# main_board_mcu.net
KiCad netlist of a schematic drawn in Altium Designer
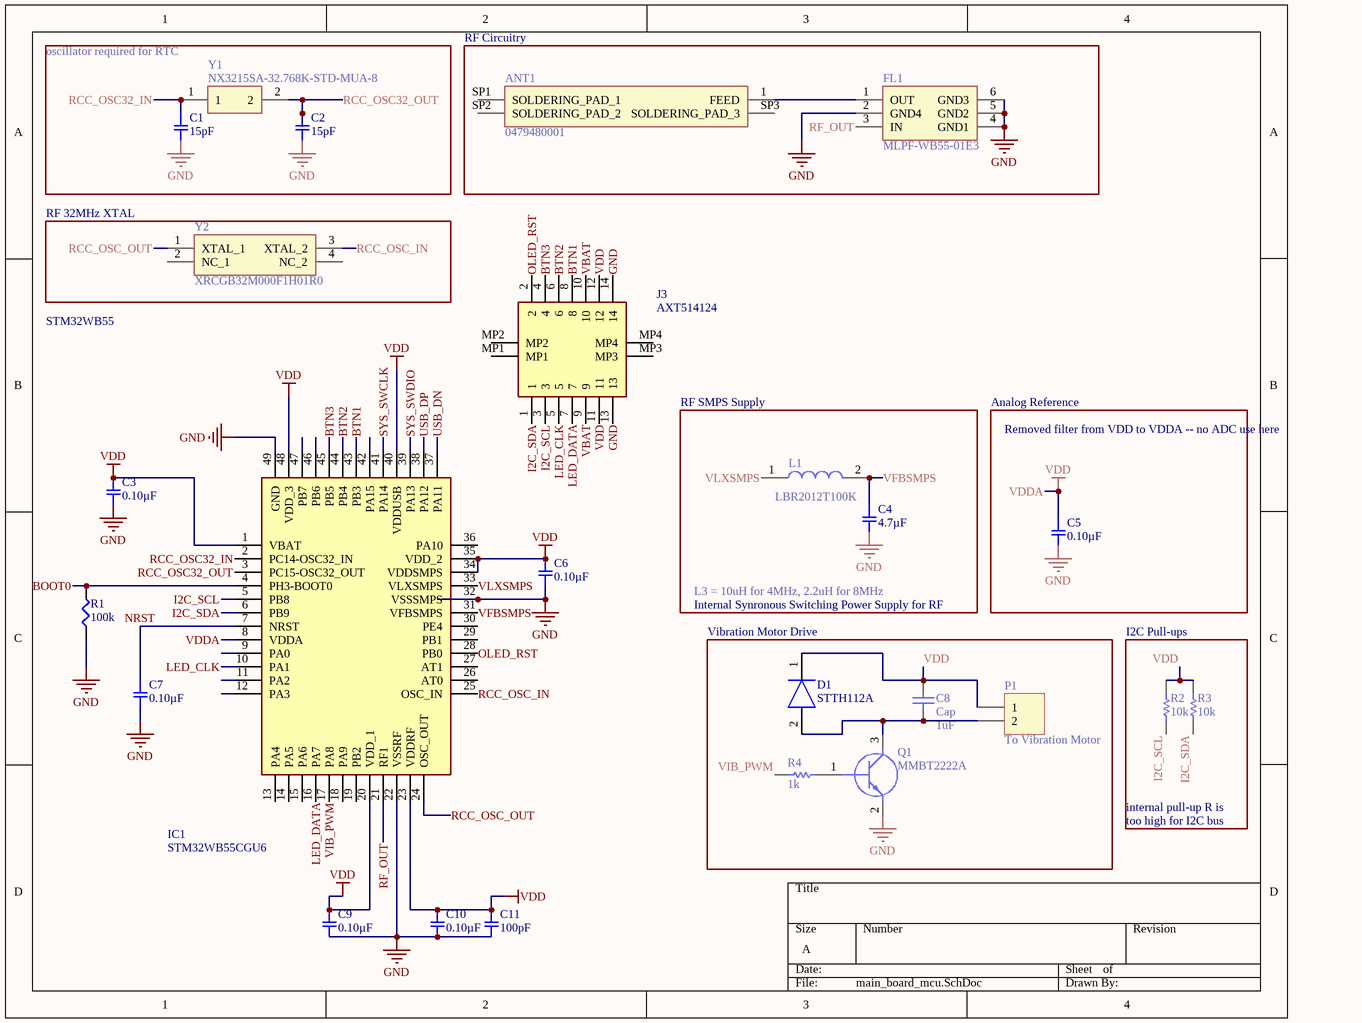
[diagram p0: main_board_mcu.SchDoc]

(export (version "E")
  (design (tool "Eeschema 10.0.6"))
  (components
    (comp (ref "ANT1")
      (value "0479480001")
      (footprint "SamacSys:0479480001")
      (description "Antenna")
      (libsource (lib "*") (part "0479480001"))
    )
    (comp (ref "C1")
      (value "15pF")
      (footprint "0402C")
      (description "CAP CER 15PF 50V NP0 0402")
      (fields
        (field (name "DIGI-KEY PART NUMBER") "490-11147-1-ND")
        (field (name "PART NUMBER") "GCM1555C1H150JA16D")
      )
      (libsource (lib "capacitor_murata_0402") (part "GCM1555C1H150JA16D"))
    )
    (comp (ref "C2")
      (value "15pF")
      (footprint "0402C")
      (description "CAP CER 15PF 50V NP0 0402")
      (fields
        (field (name "DIGI-KEY PART NUMBER") "490-11147-1-ND")
        (field (name "PART NUMBER") "GCM1555C1H150JA16D")
      )
      (libsource (lib "capacitor_murata_0402") (part "GCM1555C1H150JA16D"))
    )
    (comp (ref "C3")
      (value "0.10µF")
      (footprint "0402C")
      (description "CAP CER 0.1UF 16V X7R 0402")
      (fields
        (field (name "DIGI-KEY PART NUMBER") "490-4759-1-ND")
        (field (name "PART NUMBER") "GCM155R71C104KA55D")
      )
      (libsource (lib "capacitor_murata_0402") (part "GCM155R71C104KA55D"))
    )
    (comp (ref "C4")
      (value "4.7µF")
      (footprint "0402C")
      (description "CAP CER 4.7UF 4V X5R 0402")
      (fields
        (field (name "DIGI-KEY PART NUMBER") "490-13231-1-ND")
        (field (name "PART NUMBER") "GRM153R60G475ME15D")
      )
      (libsource (lib "capacitor_murata_0402") (part "GRM153R60G475ME15D"))
    )
    (comp (ref "C5")
      (value "0.10µF")
      (footprint "0402C")
      (description "CAP CER 0.1UF 16V X7R 0402")
      (fields
        (field (name "DIGI-KEY PART NUMBER") "490-4759-1-ND")
        (field (name "PART NUMBER") "GCM155R71C104KA55D")
      )
      (libsource (lib "capacitor_murata_0402") (part "GCM155R71C104KA55D"))
    )
    (comp (ref "C6")
      (value "0.10µF")
      (footprint "0402C")
      (description "CAP CER 0.1UF 16V X7R 0402")
      (fields
        (field (name "DIGI-KEY PART NUMBER") "490-4759-1-ND")
        (field (name "PART NUMBER") "GCM155R71C104KA55D")
      )
      (libsource (lib "capacitor_murata_0402") (part "GCM155R71C104KA55D"))
    )
    (comp (ref "C7")
      (value "0.10µF")
      (footprint "0402C")
      (description "CAP CER 0.1UF 16V X7R 0402")
      (fields
        (field (name "DIGI-KEY PART NUMBER") "490-4759-1-ND")
        (field (name "PART NUMBER") "GCM155R71C104KA55D")
      )
      (libsource (lib "capacitor_murata_0402") (part "GCM155R71C104KA55D"))
    )
    (comp (ref "C8")
      (value "Cap")
      (footprint "0402C")
      (description "Capacitor")
      (fields (field (name "ALTIUM_VALUE") "1uF") (field (name "PUBLISHER") "Altium Limited"))
      (libsource (lib "Miscellaneous Devices") (part "Cap"))
    )
    (comp (ref "C9")
      (value "0.10µF")
      (footprint "0402C")
      (description "CAP CER 0.1UF 16V X7R 0402")
      (fields
        (field (name "DIGI-KEY PART NUMBER") "490-4759-1-ND")
        (field (name "PART NUMBER") "GCM155R71C104KA55D")
      )
      (libsource (lib "capacitor_murata_0402") (part "GCM155R71C104KA55D"))
    )
    (comp (ref "C10")
      (value "0.10µF")
      (footprint "0402C")
      (description "CAP CER 0.1UF 16V X7R 0402")
      (fields
        (field (name "DIGI-KEY PART NUMBER") "490-4759-1-ND")
        (field (name "PART NUMBER") "GCM155R71C104KA55D")
      )
      (libsource (lib "capacitor_murata_0402") (part "GCM155R71C104KA55D"))
    )
    (comp (ref "C11")
      (value "100pF")
      (footprint "0402C")
      (description "CAP CER 100PF 50V NP0 0402")
      (fields
        (field (name "DIGI-KEY PART NUMBER") "490-10669-1-ND")
        (field (name "PART NUMBER") "GCM1555C1H101JA16D")
      )
      (libsource (lib "capacitor_murata_0402") (part "GCM1555C1H101JA16D"))
    )
    (comp (ref "D1")
      (value "STTH112A")
      (footprint "SamacSys:DIOM5126X265N")
      (description "Diode")
      (fields (field (name "MOUSER PART NUMBER") "511-STTH112A") (field (name "RS PART NUMBER") "0249319"))
      (libsource (lib "*") (part "STTH112A"))
    )
    (comp (ref "FL1")
      (value "MLPF-WB55-01E3")
      (footprint "SamacSys:MLPFWB5501E3")
      (description "Filter")
      (fields
        (field (name "MOUSER PART NUMBER") "511-MLPF-WB55-01E3")
        (field (name "RS PART NUMBER") "1924203")
      )
      (libsource (lib "*") (part "MLPF-WB55-01E3"))
    )
    (comp (ref "IC1")
      (value "STM32WB55CGU6")
      (footprint "QFN50P700X700X65-49N-D")
      (description "Integrated Circuit")
      (fields (field (name "MOUSER PART NUMBER") "511-STM32WB55CGU6"))
      (libsource (lib "SamacSys") (part "STM32WB55CGU6"))
    )
    (comp (ref "J3")
      (value "AXT514124")
      (footprint "SamacSys:AXT514124")
      (description "Connector")
      (fields (field (name "MOUSER PART NUMBER") "769-AXT514124"))
      (libsource (lib "*") (part "AXT514124"))
    )
    (comp (ref "L1")
      (value "LBR2012T100K")
      (footprint "INDC2012X145N")
      (description "Inductor")
      (fields (field (name "MOUSER PART NUMBER") "963-LBR2012T100K"))
      (libsource (lib "SamacSys") (part "LBR2012T100K"))
    )
    (comp (ref "P1")
      (value "To Vibration Motor")
      (footprint "HDR1X2")
      (description "Header, 2-Pin")
      (fields (field (name "PUBLISHER") "Altium Limited"))
      (libsource (lib "Miscellaneous Connectors") (part "Header 2"))
    )
    (comp (ref "Q1")
      (value "MMBT2222A")
      (footprint "SamacSys:SOT95P240X120-3N")
      (description "Transistor BJT NPN")
      (fields (field (name "MOUSER PART NUMBER") "512-MMBT2222A") (field (name "RS PART NUMBER") "7390350P"))
      (libsource (lib "*") (part "MMBT2222A"))
    )
    (comp (ref "R1")
      (value "100k")
      (footprint "0402R")
      (description "RES SMD 100K OHM 1% 1/10W 0402")
      (fields
        (field (name "PART NUMBER") "ERJ-2RKF1003X")
        (field (name "DIGI-KEY PART NUMBER") "P100KLCT-ND")
      )
      (libsource (lib "Panasonic_ERJ_0402") (part "ERJ-2RKF1003X"))
    )
    (comp (ref "R2")
      (value "10k")
      (footprint "0402R")
      (libsource (lib "glasses_full_v1_small") (part "Resistor"))
    )
    (comp (ref "R3")
      (value "10k")
      (footprint "0402R")
      (libsource (lib "glasses_full_v1_small") (part "Resistor"))
    )
    (comp (ref "R4")
      (value "1k")
      (footprint "0402R")
      (libsource (lib "glasses_full_v1_small") (part "Resistor"))
    )
    (comp (ref "Y1")
      (value "NX3215SA-32.768K-STD-MUA-8")
      (footprint "NX3215SA")
      (description "Crystal or Oscillator")
      (fields (field (name "MOUSER PART NUMBER") "344-NX3215SA32768K8"))
      (libsource (lib "SamacSys") (part "NX3215SA-32.768K-STD-MUA-8"))
    )
    (comp (ref "Y2")
      (value "XRCGB32M000F1H01R0")
      (footprint "XRCGB32M000F1H01R0")
      (description "Crystal or Oscillator")
      (fields (field (name "MOUSER PART NUMBER") "81-XRCGB32M000F1H01R"))
      (libsource (lib "SamacSys") (part "XRCGB32M000F1H01R0"))
    )
  )
  (nets
    (net (code "1") (name "/BOOT0") (class "Default")
      (node (ref "IC1") (pin "4") (pinfunction "PH3-BOOT0_4") (pintype "passive"))
      (node (ref "R1") (pin "2") (pinfunction "2_2") (pintype "passive"))
    )
    (net (code "2") (name "/BTN1") (class "Default")
      (node (ref "IC1") (pin "43") (pinfunction "PB3_43") (pintype "passive"))
      (node (ref "J3") (pin "8") (pinfunction "8_8") (pintype "passive"))
    )
    (net (code "3") (name "/BTN2") (class "Default")
      (node (ref "IC1") (pin "44") (pinfunction "PB4_44") (pintype "passive"))
      (node (ref "J3") (pin "6") (pinfunction "6_6") (pintype "passive"))
    )
    (net (code "4") (name "/BTN3") (class "Default")
      (node (ref "IC1") (pin "45") (pinfunction "PB5_45") (pintype "passive"))
      (node (ref "J3") (pin "4") (pinfunction "4_4") (pintype "passive"))
    )
    (net (code "5") (name "/I2C_SCL") (class "Default")
      (node (ref "IC1") (pin "5") (pinfunction "PB8_5") (pintype "passive"))
      (node (ref "J3") (pin "3") (pinfunction "3_3") (pintype "passive"))
      (node (ref "R2") (pin "2") (pinfunction "2_2") (pintype "passive"))
    )
    (net (code "6") (name "/I2C_SDA") (class "Default")
      (node (ref "IC1") (pin "6") (pinfunction "PB9_6") (pintype "passive"))
      (node (ref "J3") (pin "1") (pinfunction "1_1") (pintype "passive"))
      (node (ref "R3") (pin "2") (pinfunction "2_2") (pintype "passive"))
    )
    (net (code "7") (name "/LED_CLK") (class "Default")
      (node (ref "IC1") (pin "10") (pinfunction "PA1_10") (pintype "passive"))
      (node (ref "J3") (pin "5") (pinfunction "5_5") (pintype "passive"))
    )
    (net (code "8") (name "/LED_DATA") (class "Default")
      (node (ref "IC1") (pin "16") (pinfunction "PA7_16") (pintype "passive"))
      (node (ref "J3") (pin "7") (pinfunction "7_7") (pintype "passive"))
    )
    (net (code "9") (name "/NRST") (class "Default")
      (node (ref "C7") (pin "1") (pinfunction "1_1") (pintype "passive"))
      (node (ref "IC1") (pin "7") (pinfunction "NRST_7") (pintype "passive"))
    )
    (net (code "10") (name "/OLED_RST") (class "Default")
      (node (ref "IC1") (pin "28") (pinfunction "PB0_28") (pintype "passive"))
      (node (ref "J3") (pin "2") (pinfunction "2_2") (pintype "passive"))
    )
    (net (code "11") (name "/RCC_OSC32_IN") (class "Default")
      (node (ref "C1") (pin "1") (pinfunction "1_1") (pintype "passive"))
      (node (ref "IC1") (pin "2") (pinfunction "PC14-OSC32_IN_2") (pintype "passive"))
      (node (ref "Y1") (pin "1") (pinfunction "1_1") (pintype "passive"))
    )
    (net (code "12") (name "/RCC_OSC32_OUT") (class "Default")
      (node (ref "C2") (pin "1") (pinfunction "1_1") (pintype "passive"))
      (node (ref "IC1") (pin "3") (pinfunction "PC15-OSC32_OUT_3") (pintype "passive"))
      (node (ref "Y1") (pin "2") (pinfunction "2_2") (pintype "passive"))
    )
    (net (code "13") (name "/RCC_OSC_IN") (class "Default")
      (node (ref "IC1") (pin "25") (pinfunction "OSC_IN_25") (pintype "passive"))
      (node (ref "Y2") (pin "3") (pinfunction "XTAL_2_3") (pintype "passive"))
    )
    (net (code "14") (name "/RCC_OSC_OUT") (class "Default")
      (node (ref "IC1") (pin "24") (pinfunction "OSC_OUT_24") (pintype "passive"))
      (node (ref "Y2") (pin "1") (pinfunction "XTAL_1_1") (pintype "passive"))
    )
    (net (code "15") (name "/RF_OUT") (class "Default")
      (node (ref "FL1") (pin "3") (pinfunction "IN_3") (pintype "passive"))
      (node (ref "IC1") (pin "21") (pinfunction "RF1_21") (pintype "passive"))
    )
    (net (code "16") (name "/SYS_SWCLK") (class "Default")
      (node (ref "IC1") (pin "41") (pinfunction "PA14_41") (pintype "passive"))
    )
    (net (code "17") (name "/SYS_SWDIO") (class "Default")
      (node (ref "IC1") (pin "39") (pinfunction "PA13_39") (pintype "passive"))
    )
    (net (code "18") (name "/USB_DN") (class "Default")
      (node (ref "IC1") (pin "37") (pinfunction "PA11_37") (pintype "passive"))
    )
    (net (code "19") (name "/USB_DP") (class "Default")
      (node (ref "IC1") (pin "38") (pinfunction "PA12_38") (pintype "passive"))
    )
    (net (code "20") (name "/VBAT") (class "Default")
      (node (ref "J3") (pin "10") (pinfunction "10_10") (pintype "passive"))
      (node (ref "J3") (pin "9") (pinfunction "9_9") (pintype "passive"))
    )
    (net (code "21") (name "/VFBSMPS") (class "Default")
      (node (ref "C4") (pin "1") (pinfunction "1_1") (pintype "passive"))
      (node (ref "IC1") (pin "31") (pinfunction "VFBSMPS_31") (pintype "passive"))
      (node (ref "L1") (pin "2") (pinfunction "2_2") (pintype "passive"))
    )
    (net (code "22") (name "/VIB_PWM") (class "Default")
      (node (ref "IC1") (pin "17") (pinfunction "PA8_17") (pintype "passive"))
      (node (ref "R4") (pin "2") (pinfunction "2_2") (pintype "passive"))
    )
    (net (code "23") (name "/VLXSMPS") (class "Default")
      (node (ref "IC1") (pin "33") (pinfunction "VLXSMPS_33") (pintype "passive"))
      (node (ref "L1") (pin "1") (pinfunction "1_1") (pintype "passive"))
    )
    (net (code "24") (name "GND") (class "Default")
      (node (ref "C1") (pin "2") (pinfunction "2_2") (pintype "passive"))
      (node (ref "C10") (pin "2") (pinfunction "2_2") (pintype "passive"))
      (node (ref "C11") (pin "2") (pinfunction "2_2") (pintype "passive"))
      (node (ref "C2") (pin "2") (pinfunction "2_2") (pintype "passive"))
      (node (ref "C3") (pin "2") (pinfunction "2_2") (pintype "passive"))
      (node (ref "C4") (pin "2") (pinfunction "2_2") (pintype "passive"))
      (node (ref "C5") (pin "2") (pinfunction "2_2") (pintype "passive"))
      (node (ref "C6") (pin "2") (pinfunction "2_2") (pintype "passive"))
      (node (ref "C7") (pin "2") (pinfunction "2_2") (pintype "passive"))
      (node (ref "C9") (pin "2") (pinfunction "2_2") (pintype "passive"))
      (node (ref "FL1") (pin "2") (pinfunction "GND4_2") (pintype "passive"))
      (node (ref "FL1") (pin "4") (pinfunction "GND1_4") (pintype "passive"))
      (node (ref "FL1") (pin "5") (pinfunction "GND2_5") (pintype "passive"))
      (node (ref "FL1") (pin "6") (pinfunction "GND3_6") (pintype "passive"))
      (node (ref "IC1") (pin "22") (pinfunction "VSSRF_22") (pintype "passive"))
      (node (ref "IC1") (pin "32") (pinfunction "VSSSMPS_32") (pintype "passive"))
      (node (ref "IC1") (pin "49") (pinfunction "GND_49") (pintype "passive"))
      (node (ref "J3") (pin "13") (pinfunction "13_13") (pintype "passive"))
      (node (ref "J3") (pin "14") (pinfunction "14_14") (pintype "passive"))
      (node (ref "Q1") (pin "2") (pinfunction "E_2") (pintype "passive"))
      (node (ref "R1") (pin "1") (pinfunction "1_1") (pintype "passive"))
    )
    (net (code "25") (name "Net-(ANT1-FEED)") (class "Default")
      (node (ref "ANT1") (pin "1") (pinfunction "FEED_1") (pintype "passive"))
      (node (ref "FL1") (pin "1") (pinfunction "OUT_1") (pintype "passive"))
    )
    (net (code "26") (name "Net-(D1-A)") (class "Default")
      (node (ref "C8") (pin "1") (pinfunction "1_1") (pintype "passive"))
      (node (ref "D1") (pin "2") (pinfunction "A_2") (pintype "passive"))
      (node (ref "P1") (pin "2") (pinfunction "2_2") (pintype "passive"))
      (node (ref "Q1") (pin "3") (pinfunction "C_3") (pintype "passive"))
    )
    (net (code "27") (name "Net-(Q1-B)") (class "Default")
      (node (ref "Q1") (pin "1") (pinfunction "B_1") (pintype "passive"))
      (node (ref "R4") (pin "1") (pinfunction "1_1") (pintype "passive"))
    )
    (net (code "28") (name "VDD") (class "Default")
      (node (ref "C10") (pin "1") (pinfunction "1_1") (pintype "passive"))
      (node (ref "C11") (pin "1") (pinfunction "1_1") (pintype "passive"))
      (node (ref "C3") (pin "1") (pinfunction "1_1") (pintype "passive"))
      (node (ref "C5") (pin "1") (pinfunction "1_1") (pintype "passive"))
      (node (ref "C6") (pin "1") (pinfunction "1_1") (pintype "passive"))
      (node (ref "C8") (pin "2") (pinfunction "2_2") (pintype "passive"))
      (node (ref "C9") (pin "1") (pinfunction "1_1") (pintype "passive"))
      (node (ref "D1") (pin "1") (pinfunction "K_1") (pintype "passive"))
      (node (ref "IC1") (pin "1") (pinfunction "VBAT_1") (pintype "passive"))
      (node (ref "IC1") (pin "20") (pinfunction "VDD_1_20") (pintype "passive"))
      (node (ref "IC1") (pin "23") (pinfunction "VDDRF_23") (pintype "passive"))
      (node (ref "IC1") (pin "34") (pinfunction "VDDSMPS_34") (pintype "passive"))
      (node (ref "IC1") (pin "35") (pinfunction "VDD_2_35") (pintype "passive"))
      (node (ref "IC1") (pin "40") (pinfunction "VDDUSB_40") (pintype "passive"))
      (node (ref "IC1") (pin "48") (pinfunction "VDD_3_48") (pintype "passive"))
      (node (ref "IC1") (pin "8") (pinfunction "VDDA_8") (pintype "passive"))
      (node (ref "J3") (pin "11") (pinfunction "11_11") (pintype "passive"))
      (node (ref "J3") (pin "12") (pinfunction "12_12") (pintype "passive"))
      (node (ref "P1") (pin "1") (pinfunction "1_1") (pintype "passive"))
      (node (ref "R2") (pin "1") (pinfunction "1_1") (pintype "passive"))
      (node (ref "R3") (pin "1") (pinfunction "1_1") (pintype "passive"))
    )
    (net (code "29") (name "unconnected-(ANT1-SOLDERING_PAD_1-PadSP1)") (class "Default")
      (node (ref "ANT1") (pin "SP1") (pinfunction "SOLDERING_PAD_1_SP1") (pintype "passive"))
    )
    (net (code "30") (name "unconnected-(ANT1-SOLDERING_PAD_2-PadSP2)") (class "Default")
      (node (ref "ANT1") (pin "SP2") (pinfunction "SOLDERING_PAD_2_SP2") (pintype "passive"))
    )
    (net (code "31") (name "unconnected-(ANT1-SOLDERING_PAD_3-PadSP3)") (class "Default")
      (node (ref "ANT1") (pin "SP3") (pinfunction "SOLDERING_PAD_3_SP3") (pintype "passive"))
    )
    (net (code "32") (name "unconnected-(IC1-AT0-Pad26)") (class "Default")
      (node (ref "IC1") (pin "26") (pinfunction "AT0_26") (pintype "passive"))
    )
    (net (code "33") (name "unconnected-(IC1-AT1-Pad27)") (class "Default")
      (node (ref "IC1") (pin "27") (pinfunction "AT1_27") (pintype "passive"))
    )
    (net (code "34") (name "unconnected-(IC1-PA0-Pad9)") (class "Default")
      (node (ref "IC1") (pin "9") (pinfunction "PA0_9") (pintype "passive"))
    )
    (net (code "35") (name "unconnected-(IC1-PA2-Pad11)") (class "Default")
      (node (ref "IC1") (pin "11") (pinfunction "PA2_11") (pintype "passive"))
    )
    (net (code "36") (name "unconnected-(IC1-PA3-Pad12)") (class "Default")
      (node (ref "IC1") (pin "12") (pinfunction "PA3_12") (pintype "passive"))
    )
    (net (code "37") (name "unconnected-(IC1-PA4-Pad13)") (class "Default")
      (node (ref "IC1") (pin "13") (pinfunction "PA4_13") (pintype "passive"))
    )
    (net (code "38") (name "unconnected-(IC1-PA5-Pad14)") (class "Default")
      (node (ref "IC1") (pin "14") (pinfunction "PA5_14") (pintype "passive"))
    )
    (net (code "39") (name "unconnected-(IC1-PA6-Pad15)") (class "Default")
      (node (ref "IC1") (pin "15") (pinfunction "PA6_15") (pintype "passive"))
    )
    (net (code "40") (name "unconnected-(IC1-PA9-Pad18)") (class "Default")
      (node (ref "IC1") (pin "18") (pinfunction "PA9_18") (pintype "passive"))
    )
    (net (code "41") (name "unconnected-(IC1-PA10-Pad36)") (class "Default")
      (node (ref "IC1") (pin "36") (pinfunction "PA10_36") (pintype "passive"))
    )
    (net (code "42") (name "unconnected-(IC1-PA15-Pad42)") (class "Default")
      (node (ref "IC1") (pin "42") (pinfunction "PA15_42") (pintype "passive"))
    )
    (net (code "43") (name "unconnected-(IC1-PB1-Pad29)") (class "Default")
      (node (ref "IC1") (pin "29") (pinfunction "PB1_29") (pintype "passive"))
    )
    (net (code "44") (name "unconnected-(IC1-PB2-Pad19)") (class "Default")
      (node (ref "IC1") (pin "19") (pinfunction "PB2_19") (pintype "passive"))
    )
    (net (code "45") (name "unconnected-(IC1-PB6-Pad46)") (class "Default")
      (node (ref "IC1") (pin "46") (pinfunction "PB6_46") (pintype "passive"))
    )
    (net (code "46") (name "unconnected-(IC1-PB7-Pad47)") (class "Default")
      (node (ref "IC1") (pin "47") (pinfunction "PB7_47") (pintype "passive"))
    )
    (net (code "47") (name "unconnected-(IC1-PE4-Pad30)") (class "Default")
      (node (ref "IC1") (pin "30") (pinfunction "PE4_30") (pintype "passive"))
    )
    (net (code "48") (name "unconnected-(J3-PadMP1)") (class "Default")
      (node (ref "J3") (pin "MP1") (pinfunction "MP1_MP1") (pintype "passive"))
    )
    (net (code "49") (name "unconnected-(J3-PadMP2)") (class "Default")
      (node (ref "J3") (pin "MP2") (pinfunction "MP2_MP2") (pintype "passive"))
    )
    (net (code "50") (name "unconnected-(J3-PadMP3)") (class "Default")
      (node (ref "J3") (pin "MP3") (pinfunction "MP3_MP3") (pintype "passive"))
    )
    (net (code "51") (name "unconnected-(J3-PadMP4)") (class "Default")
      (node (ref "J3") (pin "MP4") (pinfunction "MP4_MP4") (pintype "passive"))
    )
    (net (code "52") (name "unconnected-(Y2-NC_1-Pad2)") (class "Default")
      (node (ref "Y2") (pin "2") (pinfunction "NC_1_2") (pintype "passive"))
    )
    (net (code "53") (name "unconnected-(Y2-NC_2-Pad4)") (class "Default")
      (node (ref "Y2") (pin "4") (pinfunction "NC_2_4") (pintype "passive"))
    )
  )
)
